# midi-tester.net
KiCad netlist of a schematic drawn in EAGLE
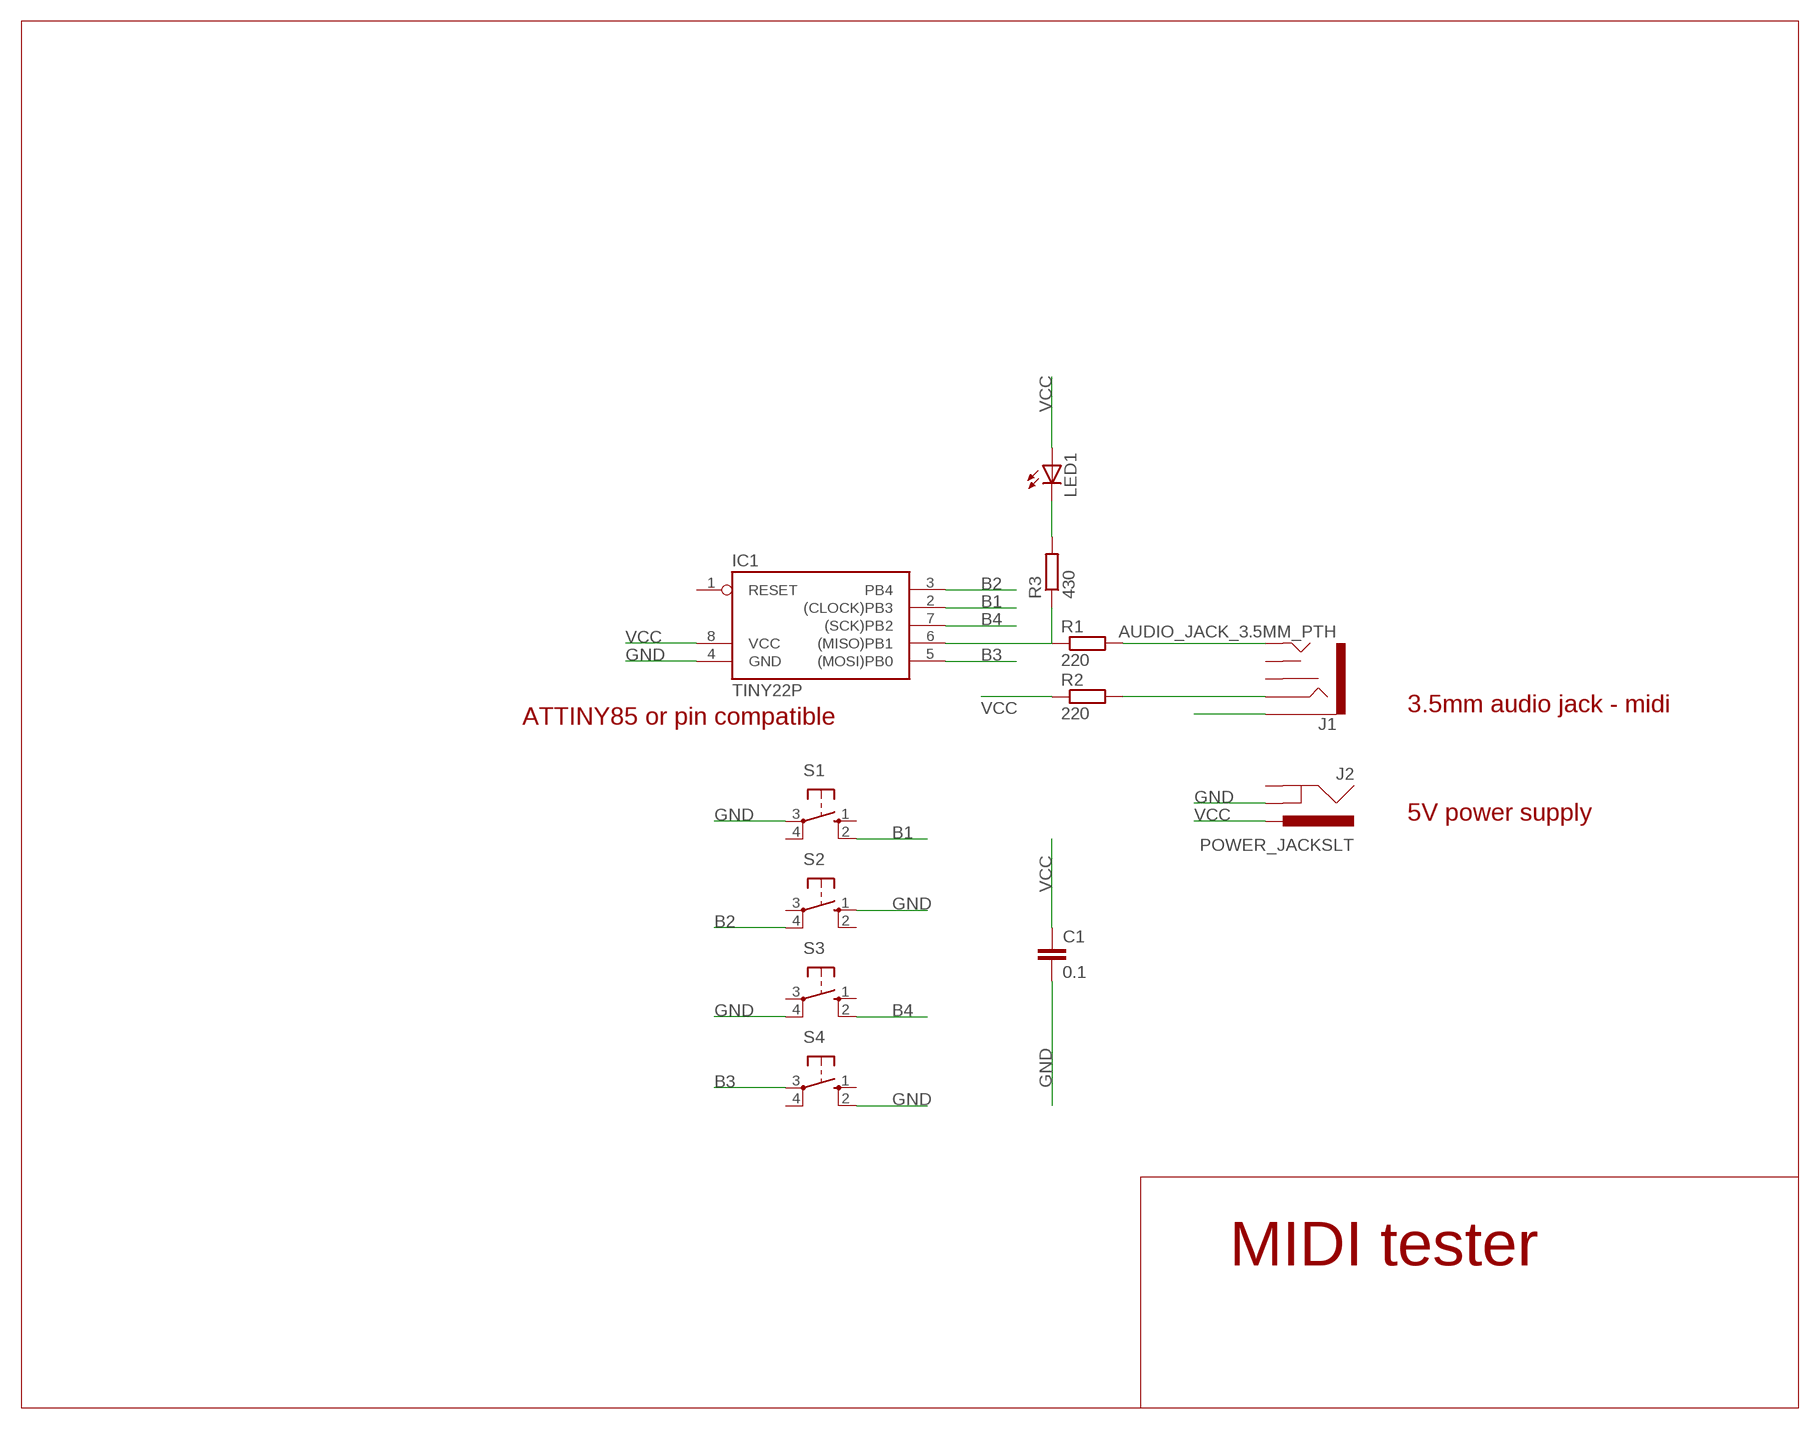
[diagram p0: schematic, sheet 1]

(export (version "E")
  (design (tool "Eeschema 10.0.6"))
  (components
    (comp (ref "C1")
      (value "0.1")
      (footprint "eagle-import:C0805")
      (libsource (lib "eagle-import") (part "C-EUC0805"))
    )
    (comp (ref "IC1")
      (value "TINY22P")
      (footprint "eagle-import:DIL08")
      (libsource (lib "eagle-import") (part "TINY22P"))
    )
    (comp (ref "J1")
      (value "AUDIO_JACK_3.5MM_PTH")
      (footprint "eagle-import:AUDIO-JACK")
      (libsource (lib "eagle-import") (part "AUDIO_JACK_3.5MM_PTH"))
    )
    (comp (ref "J2")
      (value "POWER_JACKSLT")
      (footprint "eagle-import:POWER_JACK_SLOT")
      (libsource (lib "eagle-import") (part "POWER_JACKSLT"))
    )
    (comp (ref "LED1")
      (value "LED5MM")
      (footprint "eagle-import:LED5MM")
      (libsource (lib "eagle-import") (part "LED5MM"))
    )
    (comp (ref "R1")
      (value "220")
      (footprint "eagle-import:R0805")
      (libsource (lib "eagle-import") (part "R-EU_R0805"))
    )
    (comp (ref "R2")
      (value "220")
      (footprint "eagle-import:R0805")
      (libsource (lib "eagle-import") (part "R-EU_R0805"))
    )
    (comp (ref "R3")
      (value "430")
      (footprint "eagle-import:R0805")
      (libsource (lib "eagle-import") (part "R-EU_R0805"))
    )
    (comp (ref "S1")
      (value "10-XX")
      (footprint "eagle-import:B3F-10XX")
      (fields (field (name "MPN") "B3F-1000"))
      (libsource (lib "eagle-import") (part "10-XX"))
    )
    (comp (ref "S2")
      (value "10-XX")
      (footprint "eagle-import:B3F-10XX")
      (fields (field (name "MPN") "B3F-1000"))
      (libsource (lib "eagle-import") (part "10-XX"))
    )
    (comp (ref "S3")
      (value "10-XX")
      (footprint "eagle-import:B3F-10XX")
      (fields (field (name "MPN") "B3F-1000"))
      (libsource (lib "eagle-import") (part "10-XX"))
    )
    (comp (ref "S4")
      (value "10-XX")
      (footprint "eagle-import:B3F-10XX")
      (fields (field (name "MPN") "B3F-1000"))
      (libsource (lib "eagle-import") (part "10-XX"))
    )
  )
  (nets
    (net (code "1") (name "/B1") (class "Default")
      (node (ref "IC1") (pin "2") (pinfunction "(CLOCK)PB3_2") (pintype "bidirectional"))
      (node (ref "S1") (pin "2") (pinfunction "S1_2") (pintype "passive"))
    )
    (net (code "2") (name "/B2") (class "Default")
      (node (ref "IC1") (pin "3") (pinfunction "PB4_3") (pintype "bidirectional"))
      (node (ref "S2") (pin "4") (pinfunction "P1_4") (pintype "passive"))
    )
    (net (code "3") (name "/B3") (class "Default")
      (node (ref "IC1") (pin "5") (pinfunction "(MOSI)PB0_5") (pintype "bidirectional"))
      (node (ref "S4") (pin "3") (pinfunction "P_3") (pintype "passive"))
    )
    (net (code "4") (name "/B4") (class "Default")
      (node (ref "IC1") (pin "7") (pinfunction "(SCK)PB2_7") (pintype "bidirectional"))
      (node (ref "S3") (pin "2") (pinfunction "S1_2") (pintype "passive"))
    )
    (net (code "5") (name "/GND") (class "Default")
      (node (ref "C1") (pin "2") (pinfunction "2_2") (pintype "passive"))
      (node (ref "IC1") (pin "4") (pinfunction "GND_4") (pintype "power_in"))
      (node (ref "J1") (pin "SLEEVE") (pinfunction "SLEEVE_SLEEVE") (pintype "bidirectional"))
      (node (ref "J2") (pin "GND@1") (pinfunction "GNDBREAK_GND@1") (pintype "bidirectional"))
      (node (ref "S1") (pin "3") (pinfunction "P_3") (pintype "passive"))
      (node (ref "S2") (pin "1") (pinfunction "S_1") (pintype "passive"))
      (node (ref "S3") (pin "4") (pinfunction "P1_4") (pintype "passive"))
      (node (ref "S4") (pin "2") (pinfunction "S1_2") (pintype "passive"))
    )
    (net (code "6") (name "/VCC") (class "Default")
      (node (ref "C1") (pin "1") (pinfunction "1_1") (pintype "passive"))
      (node (ref "IC1") (pin "8") (pinfunction "VCC_8") (pintype "power_in"))
      (node (ref "J2") (pin "PWR") (pinfunction "PWR_PWR") (pintype "bidirectional"))
      (node (ref "LED1") (pin "A") (pinfunction "A_A") (pintype "passive"))
      (node (ref "R2") (pin "1") (pinfunction "1_1") (pintype "passive"))
    )
    (net (code "7") (name "Net-(IC1-(MISO)PB1)") (class "Default")
      (node (ref "IC1") (pin "6") (pinfunction "(MISO)PB1_6") (pintype "bidirectional"))
      (node (ref "R1") (pin "1") (pinfunction "1_1") (pintype "passive"))
      (node (ref "R3") (pin "1") (pinfunction "1_1") (pintype "passive"))
    )
    (net (code "8") (name "Net-(J1-PadRING)") (class "Default")
      (node (ref "J1") (pin "RING") (pinfunction "RING_RING") (pintype "bidirectional"))
      (node (ref "R2") (pin "2") (pinfunction "2_2") (pintype "passive"))
    )
    (net (code "9") (name "Net-(J1-PadTIP)") (class "Default")
      (node (ref "J1") (pin "TIP") (pinfunction "TIP_TIP") (pintype "bidirectional"))
      (node (ref "R1") (pin "2") (pinfunction "2_2") (pintype "passive"))
    )
    (net (code "10") (name "Net-(LED1-C)") (class "Default")
      (node (ref "LED1") (pin "K") (pinfunction "C_K") (pintype "passive"))
      (node (ref "R3") (pin "2") (pinfunction "2_2") (pintype "passive"))
    )
    (net (code "11") (name "unconnected-(IC1-RESET-Pad1)") (class "Default")
      (node (ref "IC1") (pin "1") (pinfunction "RESET_1") (pintype "input"))
    )
    (net (code "12") (name "unconnected-(J1-PadRSH)") (class "Default")
      (node (ref "J1") (pin "RSH") (pinfunction "RSH_RSH") (pintype "bidirectional"))
    )
    (net (code "13") (name "unconnected-(J1-PadTSH)") (class "Default")
      (node (ref "J1") (pin "TSH") (pinfunction "TSH_TSH") (pintype "bidirectional"))
    )
    (net (code "14") (name "unconnected-(J2-GND-PadGND@2)") (class "Default")
      (node (ref "J2") (pin "GND@2") (pinfunction "GND_GND@2") (pintype "bidirectional"))
    )
    (net (code "15") (name "unconnected-(S1-P1-Pad4)") (class "Default")
      (node (ref "S1") (pin "4") (pinfunction "P1_4") (pintype "passive"))
    )
    (net (code "16") (name "unconnected-(S1-S-Pad1)") (class "Default")
      (node (ref "S1") (pin "1") (pinfunction "S_1") (pintype "passive"))
    )
    (net (code "17") (name "unconnected-(S2-P-Pad3)") (class "Default")
      (node (ref "S2") (pin "3") (pinfunction "P_3") (pintype "passive"))
    )
    (net (code "18") (name "unconnected-(S2-S1-Pad2)") (class "Default")
      (node (ref "S2") (pin "2") (pinfunction "S1_2") (pintype "passive"))
    )
    (net (code "19") (name "unconnected-(S3-P-Pad3)") (class "Default")
      (node (ref "S3") (pin "3") (pinfunction "P_3") (pintype "passive"))
    )
    (net (code "20") (name "unconnected-(S3-S-Pad1)") (class "Default")
      (node (ref "S3") (pin "1") (pinfunction "S_1") (pintype "passive"))
    )
    (net (code "21") (name "unconnected-(S4-P1-Pad4)") (class "Default")
      (node (ref "S4") (pin "4") (pinfunction "P1_4") (pintype "passive"))
    )
    (net (code "22") (name "unconnected-(S4-S-Pad1)") (class "Default")
      (node (ref "S4") (pin "1") (pinfunction "S_1") (pintype "passive"))
    )
  )
)
